# LUMW.net
KiCad netlist of a schematic drawn in Altium Designer
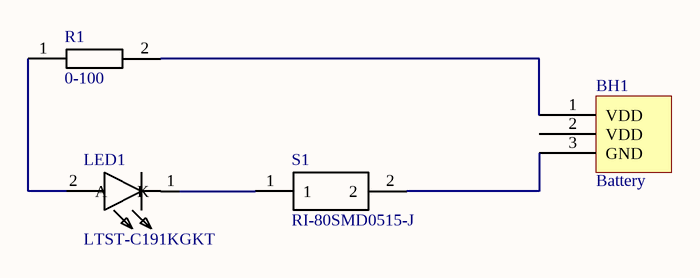
[diagram p0: LUMW.SchDoc]

(export (version "E")
  (design (tool "Eeschema 10.0.6"))
  (components
    (comp (ref "BH1")
      (value "Battery")
      (footprint "BHX1-1025-PC")
      (description "Battery Holder for BK-870")
      (libsource (lib "BK-870-NDSch") (part "BH?"))
    )
    (comp (ref "LED1")
      (value "LTST-C191KGKT")
      (footprint "SamacSys:LEDC1608X55N")
      (description "LED")
      (fields
        (field (name "MOUSER PART NUMBER") "859-LTST-C191KGKT")
        (field (name "RS PART NUMBER") "6921010P")
      )
      (libsource (lib "*") (part "LTST-C191KGKT"))
    )
    (comp (ref "R1")
      (value "0-100")
      (footprint "SamacSys:RESC1005X40N")
      (description "Resistor")
      (fields (field (name "MANUFACTURER_PART_NUMBER") "RMCF0402ZT0R00"))
      (libsource (lib "*") (part "RMCF0402ZT0R00"))
    )
    (comp (ref "S1")
      (value "RI-80SMD0515-J")
      (footprint "SamacSys:RI80SMD0510J")
      (description "Switch")
      (fields (field (name "MOUSER PART NUMBER") "816-RI-80SMD0515-J"))
      (libsource (lib "*") (part "RI-80SMD0515-J"))
    )
  )
  (nets
    (net (code "1") (name "Net-(BH1-GND)") (class "Default")
      (node (ref "BH1") (pin "3") (pinfunction "GND_3") (pintype "passive"))
      (node (ref "S1") (pin "2") (pinfunction "2_2") (pintype "passive"))
    )
    (net (code "2") (name "Net-(BH1-VDD-Pad1)") (class "Default")
      (node (ref "BH1") (pin "1") (pinfunction "VDD_1") (pintype "passive"))
      (node (ref "R1") (pin "2") (pinfunction "2_2") (pintype "passive"))
    )
    (net (code "3") (name "Net-(LED1-A)") (class "Default")
      (node (ref "LED1") (pin "2") (pinfunction "A_2") (pintype "passive"))
      (node (ref "R1") (pin "1") (pinfunction "1_1") (pintype "passive"))
    )
    (net (code "4") (name "Net-(LED1-K)") (class "Default")
      (node (ref "LED1") (pin "1") (pinfunction "K_1") (pintype "passive"))
      (node (ref "S1") (pin "1") (pinfunction "1_1") (pintype "passive"))
    )
    (net (code "5") (name "unconnected-(BH1-VDD-Pad2)") (class "Default")
      (node (ref "BH1") (pin "2") (pinfunction "VDD_2") (pintype "passive"))
    )
  )
)
